# tester_rp2040.net
KiCad netlist of a schematic drawn in EAGLE
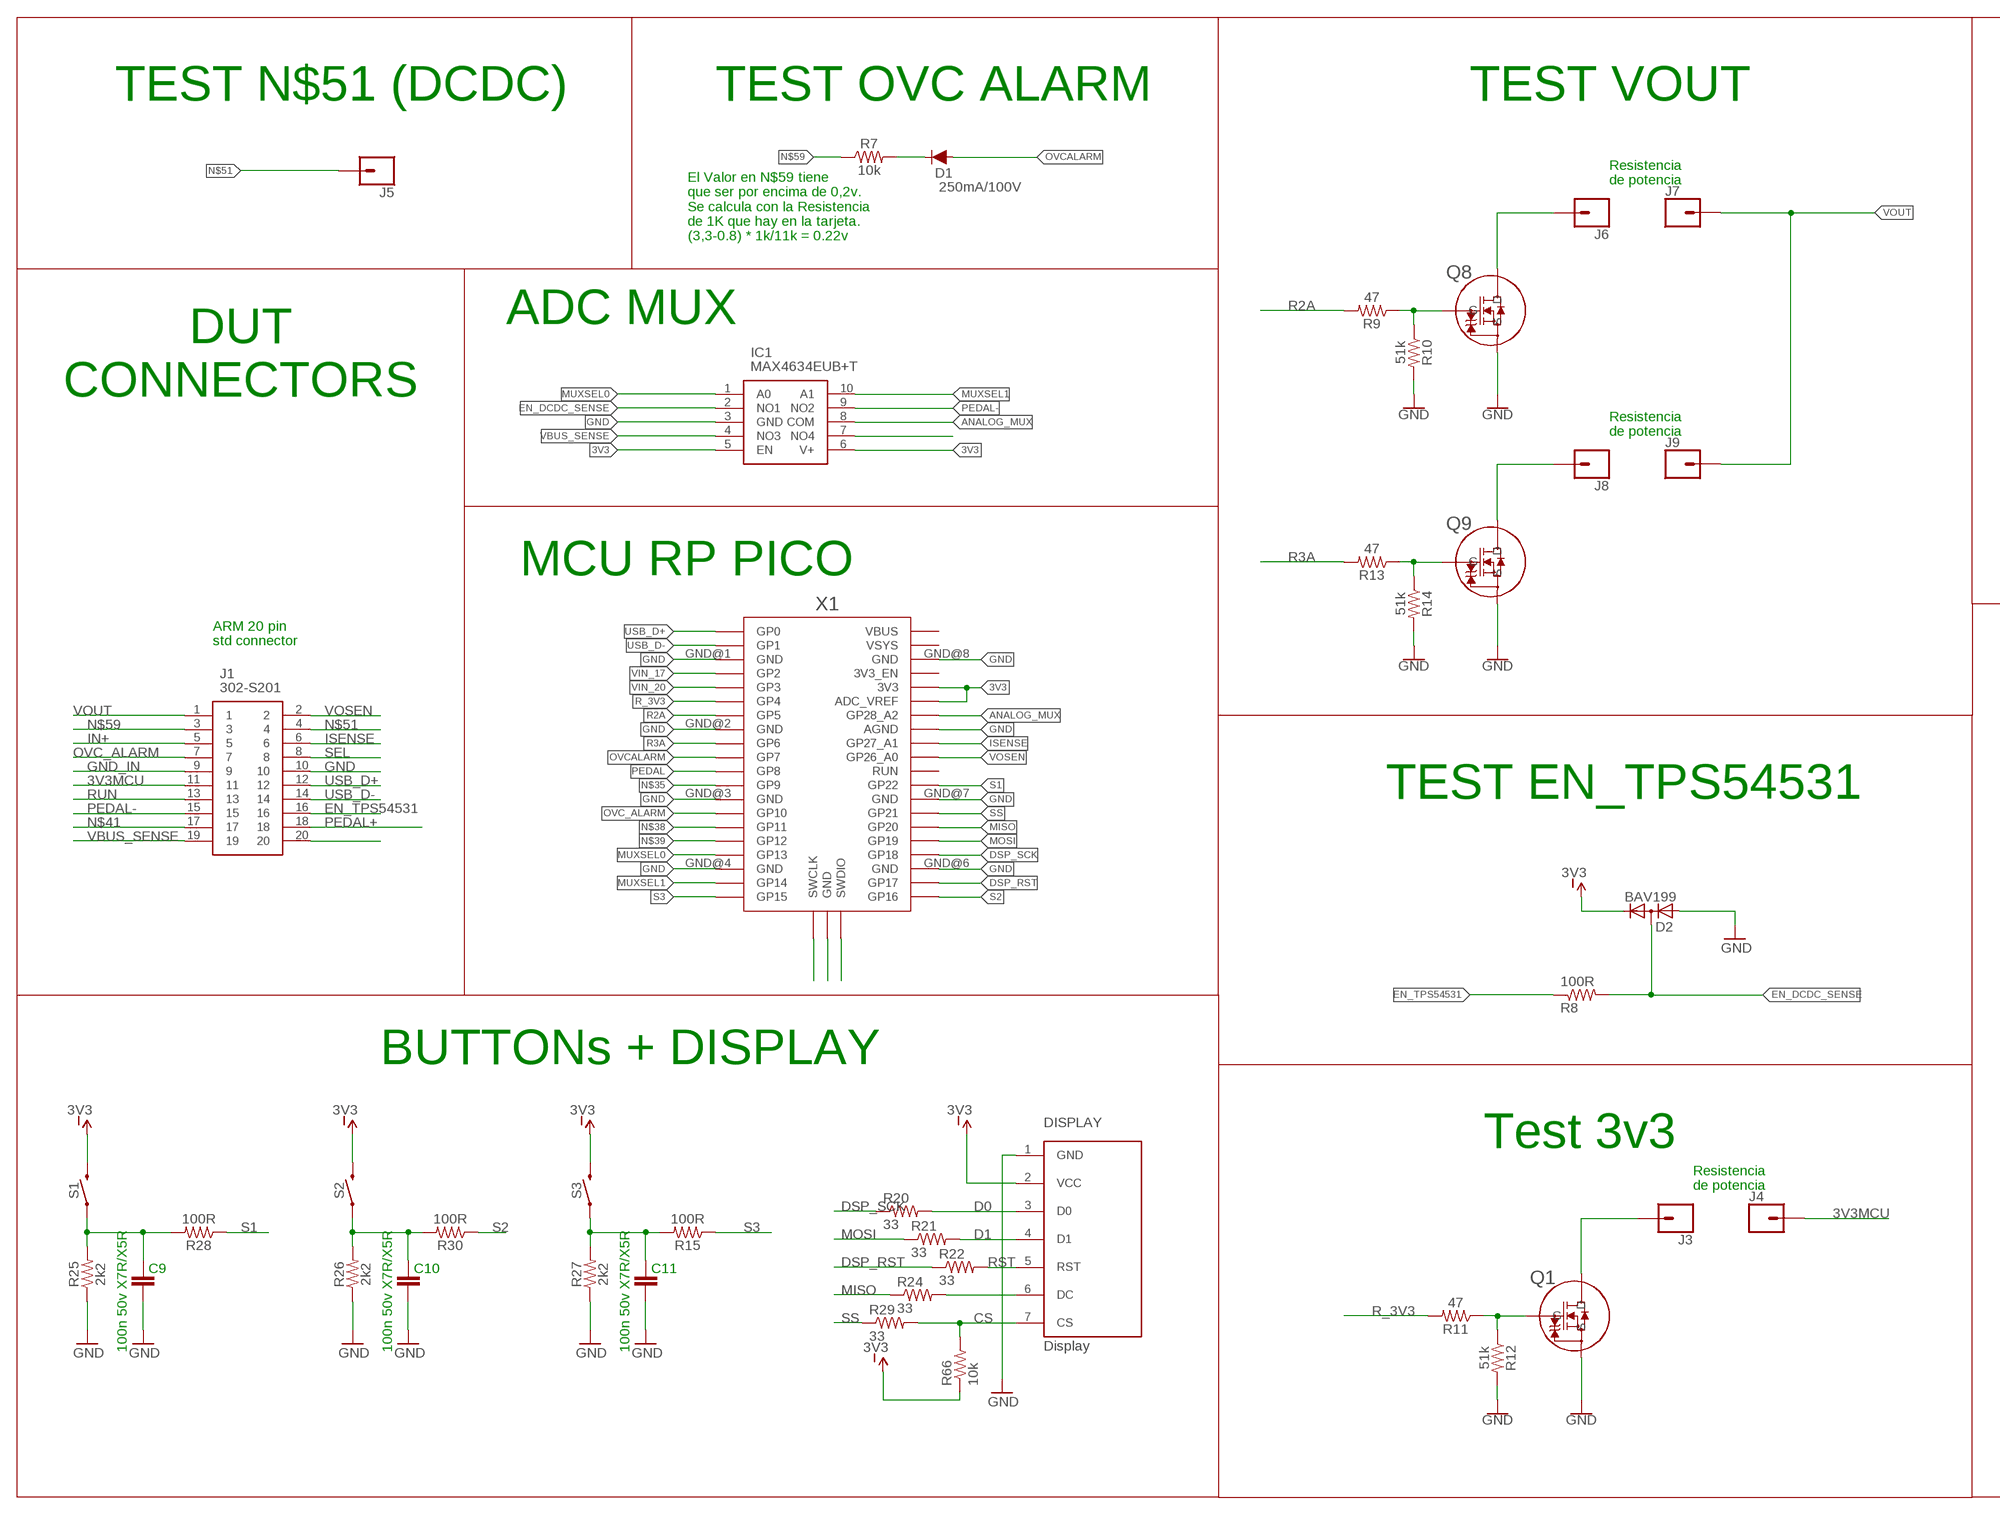
[diagram p0: schematic, sheet 1, part 1 of 2]
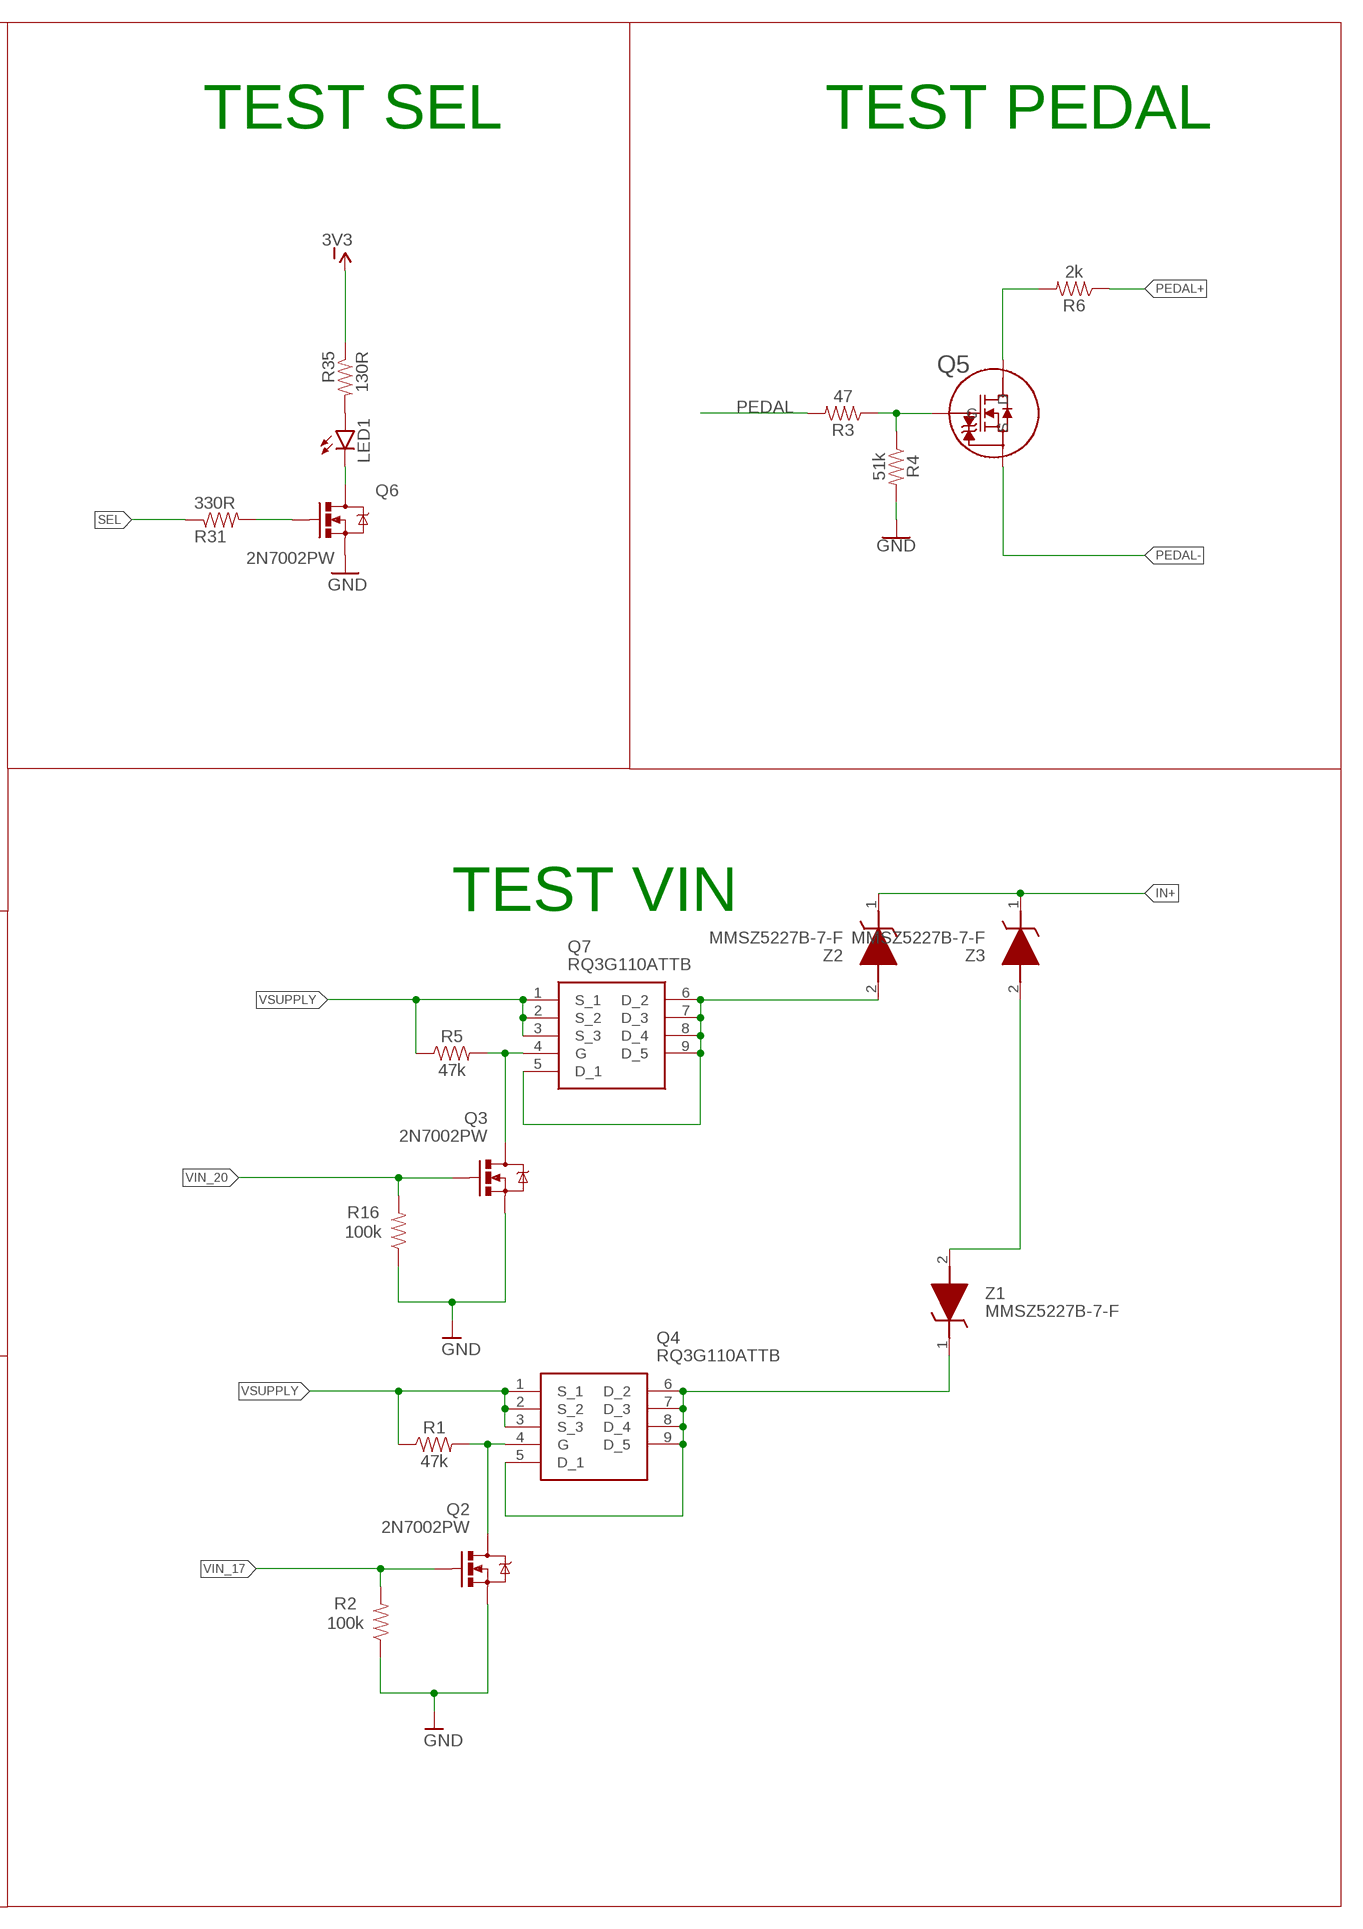
[diagram p1: schematic, sheet 1, part 2 of 2]

(export (version "E")
  (design (tool "Eeschema 10.0.6"))
  (components
    (comp (ref "C9")
      (value "100n 50v X7R/X5R")
      (footprint "eagle-import:0805")
      (libsource (lib "eagle-import") (part "CAP0805"))
    )
    (comp (ref "C10")
      (value "100n 50v X7R/X5R")
      (footprint "eagle-import:0805")
      (libsource (lib "eagle-import") (part "CAP0805"))
    )
    (comp (ref "C11")
      (value "100n 50v X7R/X5R")
      (footprint "eagle-import:0805")
      (libsource (lib "eagle-import") (part "CAP0805"))
    )
    (comp (ref "D1")
      (value "250mA/100V")
      (footprint "eagle-import:SOD-323")
      (libsource (lib "eagle-import") (part "DIODE-BAS16J"))
    )
    (comp (ref "D2")
      (value "BAV199")
      (footprint "eagle-import:SOT23")
      (libsource (lib "eagle-import") (part "BAV199"))
    )
    (comp (ref "DISPLAY")
      (value "Display")
      (footprint "eagle-import:OLED_LCD")
      (libsource (lib "eagle-import") (part "OLED_LCD"))
    )
    (comp (ref "IC1")
      (value "MAX4634EUB+T")
      (footprint "eagle-import:SOP50P490X110-10N")
      (fields (field (name "MOUSER_PART_NUMBER") "700-MAX4634EUBT"))
      (libsource (lib "eagle-import") (part "MAX4634EUB+T"))
    )
    (comp (ref "J1")
      (value "302-S201")
      (footprint "eagle-import:SHDR20W66P254_2X10_3300X905X90")
      (libsource (lib "eagle-import") (part "302-S201"))
    )
    (comp (ref "J3")
      (value "CONN_01")
      (footprint "eagle-import:1X01")
      (libsource (lib "eagle-import") (part "CONN_01"))
    )
    (comp (ref "J4")
      (value "CONN_01")
      (footprint "eagle-import:1X01")
      (libsource (lib "eagle-import") (part "CONN_01"))
    )
    (comp (ref "J5")
      (value "CONN_01")
      (footprint "eagle-import:1X01")
      (libsource (lib "eagle-import") (part "CONN_01"))
    )
    (comp (ref "J6")
      (value "CONN_01")
      (footprint "eagle-import:1X01")
      (libsource (lib "eagle-import") (part "CONN_01"))
    )
    (comp (ref "J7")
      (value "CONN_01")
      (footprint "eagle-import:1X01")
      (libsource (lib "eagle-import") (part "CONN_01"))
    )
    (comp (ref "J8")
      (value "CONN_01")
      (footprint "eagle-import:1X01")
      (libsource (lib "eagle-import") (part "CONN_01"))
    )
    (comp (ref "J9")
      (value "CONN_01")
      (footprint "eagle-import:1X01")
      (libsource (lib "eagle-import") (part "CONN_01"))
    )
    (comp (ref "LED1")
      (value "LED3MM")
      (footprint "eagle-import:LED3MM")
      (libsource (lib "eagle-import") (part "LED3MM"))
    )
    (comp (ref "Q1")
      (value "PJA3416AE_R1_00001")
      (footprint "eagle-import:SOT23_PJA3416_PNJ")
      (fields (field (name "COPYRIGHT") "Copyright (C) 2022 Ultra Librarian. All rights reserved."))
      (libsource (lib "eagle-import") (part "PJA3416AE_R1_00001"))
    )
    (comp (ref "Q2")
      (value "2N7002PW")
      (footprint "eagle-import:SOT323")
      (libsource (lib "eagle-import") (part "MOSFET-NCHANNEL2N7002PW"))
    )
    (comp (ref "Q3")
      (value "2N7002PW")
      (footprint "eagle-import:SOT323")
      (libsource (lib "eagle-import") (part "MOSFET-NCHANNEL2N7002PW"))
    )
    (comp (ref "Q4")
      (value "RQ3G110ATTB")
      (footprint "eagle-import:RQ3G110ATTB")
      (fields (field (name "MOUSER_PART_NUMBER") "755-RQ3G110ATTB"))
      (libsource (lib "eagle-import") (part "RQ3G110ATTB"))
    )
    (comp (ref "Q5")
      (value "PJA3416AE_R1_00001")
      (footprint "eagle-import:SOT23_PJA3416_PNJ")
      (fields (field (name "COPYRIGHT") "Copyright (C) 2022 Ultra Librarian. All rights reserved."))
      (libsource (lib "eagle-import") (part "PJA3416AE_R1_00001"))
    )
    (comp (ref "Q6")
      (value "2N7002PW")
      (footprint "eagle-import:SOT323")
      (libsource (lib "eagle-import") (part "MOSFET-NCHANNEL2N7002PW"))
    )
    (comp (ref "Q7")
      (value "RQ3G110ATTB")
      (footprint "eagle-import:RQ3G110ATTB")
      (fields (field (name "MOUSER_PART_NUMBER") "755-RQ3G110ATTB"))
      (libsource (lib "eagle-import") (part "RQ3G110ATTB"))
    )
    (comp (ref "Q8")
      (value "PJA3416AE_R1_00001")
      (footprint "eagle-import:SOT23_PJA3416_PNJ")
      (fields (field (name "COPYRIGHT") "Copyright (C) 2022 Ultra Librarian. All rights reserved."))
      (libsource (lib "eagle-import") (part "PJA3416AE_R1_00001"))
    )
    (comp (ref "Q9")
      (value "PJA3416AE_R1_00001")
      (footprint "eagle-import:SOT23_PJA3416_PNJ")
      (fields (field (name "COPYRIGHT") "Copyright (C) 2022 Ultra Librarian. All rights reserved."))
      (libsource (lib "eagle-import") (part "PJA3416AE_R1_00001"))
    )
    (comp (ref "R1")
      (value "47k")
      (footprint "eagle-import:0402")
      (libsource (lib "eagle-import") (part "RESISTOR0402"))
    )
    (comp (ref "R2")
      (value "100k")
      (footprint "eagle-import:0402")
      (libsource (lib "eagle-import") (part "RESISTOR0402"))
    )
    (comp (ref "R3")
      (value "47")
      (footprint "eagle-import:0805")
      (libsource (lib "eagle-import") (part "RESISTOR0805"))
    )
    (comp (ref "R4")
      (value "51k")
      (footprint "eagle-import:0805")
      (libsource (lib "eagle-import") (part "RESISTOR0805"))
    )
    (comp (ref "R5")
      (value "47k")
      (footprint "eagle-import:0402")
      (libsource (lib "eagle-import") (part "RESISTOR0402"))
    )
    (comp (ref "R6")
      (value "2k")
      (footprint "eagle-import:0805")
      (libsource (lib "eagle-import") (part "RESISTOR0805"))
    )
    (comp (ref "R7")
      (value "10k")
      (footprint "eagle-import:0805")
      (libsource (lib "eagle-import") (part "RESISTOR0805"))
    )
    (comp (ref "R8")
      (value "100R")
      (footprint "eagle-import:0805")
      (libsource (lib "eagle-import") (part "RESISTOR0805"))
    )
    (comp (ref "R9")
      (value "47")
      (footprint "eagle-import:0805")
      (libsource (lib "eagle-import") (part "RESISTOR0805"))
    )
    (comp (ref "R10")
      (value "51k")
      (footprint "eagle-import:0805")
      (libsource (lib "eagle-import") (part "RESISTOR0805"))
    )
    (comp (ref "R11")
      (value "47")
      (footprint "eagle-import:0805")
      (libsource (lib "eagle-import") (part "RESISTOR0805"))
    )
    (comp (ref "R12")
      (value "51k")
      (footprint "eagle-import:0805")
      (libsource (lib "eagle-import") (part "RESISTOR0805"))
    )
    (comp (ref "R13")
      (value "47")
      (footprint "eagle-import:0805")
      (libsource (lib "eagle-import") (part "RESISTOR0805"))
    )
    (comp (ref "R14")
      (value "51k")
      (footprint "eagle-import:0805")
      (libsource (lib "eagle-import") (part "RESISTOR0805"))
    )
    (comp (ref "R15")
      (value "100R")
      (footprint "eagle-import:0805")
      (libsource (lib "eagle-import") (part "RESISTOR0805"))
    )
    (comp (ref "R16")
      (value "100k")
      (footprint "eagle-import:0402")
      (libsource (lib "eagle-import") (part "RESISTOR0402"))
    )
    (comp (ref "R20")
      (value "33")
      (footprint "eagle-import:0805")
      (libsource (lib "eagle-import") (part "RESISTOR0805"))
    )
    (comp (ref "R21")
      (value "33")
      (footprint "eagle-import:0805")
      (libsource (lib "eagle-import") (part "RESISTOR0805"))
    )
    (comp (ref "R22")
      (value "33")
      (footprint "eagle-import:0805")
      (libsource (lib "eagle-import") (part "RESISTOR0805"))
    )
    (comp (ref "R24")
      (value "33")
      (footprint "eagle-import:0805")
      (libsource (lib "eagle-import") (part "RESISTOR0805"))
    )
    (comp (ref "R25")
      (value "2k2")
      (footprint "eagle-import:0805")
      (libsource (lib "eagle-import") (part "RESISTOR0805"))
    )
    (comp (ref "R26")
      (value "2k2")
      (footprint "eagle-import:0805")
      (libsource (lib "eagle-import") (part "RESISTOR0805"))
    )
    (comp (ref "R27")
      (value "2k2")
      (footprint "eagle-import:0805")
      (libsource (lib "eagle-import") (part "RESISTOR0805"))
    )
    (comp (ref "R28")
      (value "100R")
      (footprint "eagle-import:0805")
      (libsource (lib "eagle-import") (part "RESISTOR0805"))
    )
    (comp (ref "R29")
      (value "33")
      (footprint "eagle-import:0805")
      (libsource (lib "eagle-import") (part "RESISTOR0805"))
    )
    (comp (ref "R30")
      (value "100R")
      (footprint "eagle-import:0805")
      (libsource (lib "eagle-import") (part "RESISTOR0805"))
    )
    (comp (ref "R31")
      (value "330R")
      (footprint "eagle-import:0805")
      (libsource (lib "eagle-import") (part "RESISTOR0805"))
    )
    (comp (ref "R35")
      (value "130R")
      (footprint "eagle-import:0805")
      (libsource (lib "eagle-import") (part "RESISTOR0805"))
    )
    (comp (ref "R66")
      (value "10k")
      (footprint "eagle-import:0805")
      (libsource (lib "eagle-import") (part "RESISTOR0805"))
    )
    (comp (ref "S1")
      (value "MOMENTARY-SWITCH-SPST-SMD-5.2MM")
      (footprint "eagle-import:TACTILE_SWITCH_SMD_5.2MM")
      (libsource (lib "eagle-import") (part "MOMENTARY-SWITCH-SPST-SMD-5.2MM"))
    )
    (comp (ref "S2")
      (value "MOMENTARY-SWITCH-SPST-SMD-5.2MM")
      (footprint "eagle-import:TACTILE_SWITCH_SMD_5.2MM")
      (libsource (lib "eagle-import") (part "MOMENTARY-SWITCH-SPST-SMD-5.2MM"))
    )
    (comp (ref "S3")
      (value "MOMENTARY-SWITCH-SPST-SMD-5.2MM")
      (footprint "eagle-import:TACTILE_SWITCH_SMD_5.2MM")
      (libsource (lib "eagle-import") (part "MOMENTARY-SWITCH-SPST-SMD-5.2MM"))
    )
    (comp (ref "X1")
      (value "RPI_PICO_IG-TH")
      (footprint "eagle-import:RPI_PICO_TH")
      (libsource (lib "eagle-import") (part "RPI_PICO_IG-TH"))
    )
    (comp (ref "Z1")
      (value "MMSZ5227B-7-F")
      (footprint "eagle-import:SOD3716X135N")
      (fields (field (name "MOUSER_PART_NUMBER") "621-MMSZ5227B-F"))
      (libsource (lib "eagle-import") (part "MMSZ5227B-7-F"))
    )
    (comp (ref "Z2")
      (value "MMSZ5227B-7-F")
      (footprint "eagle-import:SOD3716X135N")
      (fields (field (name "MOUSER_PART_NUMBER") "621-MMSZ5227B-F"))
      (libsource (lib "eagle-import") (part "MMSZ5227B-7-F"))
    )
    (comp (ref "Z3")
      (value "MMSZ5227B-7-F")
      (footprint "eagle-import:SOD3716X135N")
      (fields (field (name "MOUSER_PART_NUMBER") "621-MMSZ5227B-F"))
      (libsource (lib "eagle-import") (part "MMSZ5227B-7-F"))
    )
  )
  (nets
    (net (code "1") (name "/3V3MCU") (class "Default")
      (node (ref "J1") (pin "11") (pinfunction "11_11") (pintype "bidirectional"))
      (node (ref "J4") (pin "1") (pinfunction "1_1") (pintype "passive"))
    )
    (net (code "2") (name "/CS") (class "Default")
      (node (ref "DISPLAY") (pin "7") (pinfunction "CS_7") (pintype "bidirectional"))
      (node (ref "R29") (pin "2") (pinfunction "2_2") (pintype "passive"))
      (node (ref "R66") (pin "2") (pinfunction "2_2") (pintype "passive"))
    )
    (net (code "3") (name "/D0") (class "Default")
      (node (ref "DISPLAY") (pin "3") (pinfunction "D0_3") (pintype "bidirectional"))
      (node (ref "R20") (pin "2") (pinfunction "2_2") (pintype "passive"))
    )
    (net (code "4") (name "/D1") (class "Default")
      (node (ref "DISPLAY") (pin "4") (pinfunction "D1_4") (pintype "bidirectional"))
      (node (ref "R21") (pin "2") (pinfunction "2_2") (pintype "passive"))
    )
    (net (code "5") (name "/GND_IN") (class "Default")
      (node (ref "J1") (pin "9") (pinfunction "9_9") (pintype "bidirectional"))
    )
    (net (code "6") (name "/N$41") (class "Default")
      (node (ref "J1") (pin "17") (pinfunction "17_17") (pintype "bidirectional"))
    )
    (net (code "7") (name "/RST") (class "Default")
      (node (ref "DISPLAY") (pin "5") (pinfunction "RST_5") (pintype "bidirectional"))
      (node (ref "R22") (pin "2") (pinfunction "2_2") (pintype "passive"))
    )
    (net (code "8") (name "/RUN") (class "Default")
      (node (ref "J1") (pin "13") (pinfunction "13_13") (pintype "bidirectional"))
    )
    (net (code "9") (name "3V3") (class "Default")
      (node (ref "D2") (pin "2") (pinfunction "C_2") (pintype "passive"))
      (node (ref "DISPLAY") (pin "2") (pinfunction "VCC_2") (pintype "bidirectional"))
      (node (ref "IC1") (pin "5") (pinfunction "EN_5") (pintype "bidirectional"))
      (node (ref "IC1") (pin "6") (pinfunction "V+_6") (pintype "bidirectional"))
      (node (ref "R35") (pin "1") (pinfunction "1_1") (pintype "passive"))
      (node (ref "R66") (pin "1") (pinfunction "1_1") (pintype "passive"))
      (node (ref "S1") (pin "3") (pinfunction "2_3") (pintype "passive"))
      (node (ref "S2") (pin "3") (pinfunction "2_3") (pintype "passive"))
      (node (ref "S3") (pin "3") (pinfunction "2_3") (pintype "passive"))
      (node (ref "X1") (pin "3V3") (pinfunction "3V3_3V3") (pintype "bidirectional"))
      (node (ref "X1") (pin "ADC_VREF") (pinfunction "ADC_VREF_ADC_VREF") (pintype "bidirectional"))
    )
    (net (code "10") (name "ANALOG_MUX") (class "Default")
      (node (ref "IC1") (pin "8") (pinfunction "COM_8") (pintype "bidirectional"))
      (node (ref "X1") (pin "GP28_A2") (pinfunction "GP28_A2_GP28_A2") (pintype "bidirectional"))
    )
    (net (code "11") (name "DSP_RST") (class "Default")
      (node (ref "R22") (pin "1") (pinfunction "1_1") (pintype "passive"))
      (node (ref "X1") (pin "GP17") (pinfunction "GP17_GP17") (pintype "bidirectional"))
    )
    (net (code "12") (name "DSP_SCK") (class "Default")
      (node (ref "R20") (pin "1") (pinfunction "1_1") (pintype "passive"))
      (node (ref "X1") (pin "GP18") (pinfunction "GP18_GP18") (pintype "bidirectional"))
    )
    (net (code "13") (name "EN_DCDC_SENSE") (class "Default")
      (node (ref "D2") (pin "3") (pinfunction "AC_3") (pintype "passive"))
      (node (ref "IC1") (pin "2") (pinfunction "NO1_2") (pintype "bidirectional"))
      (node (ref "R8") (pin "2") (pinfunction "2_2") (pintype "passive"))
    )
    (net (code "14") (name "EN_TPS54531") (class "Default")
      (node (ref "J1") (pin "16") (pinfunction "16_16") (pintype "bidirectional"))
      (node (ref "R8") (pin "1") (pinfunction "1_1") (pintype "passive"))
    )
    (net (code "15") (name "GND") (class "Default")
      (node (ref "C10") (pin "1") (pinfunction "1_1") (pintype "passive"))
      (node (ref "C11") (pin "1") (pinfunction "1_1") (pintype "passive"))
      (node (ref "C9") (pin "1") (pinfunction "1_1") (pintype "passive"))
      (node (ref "D2") (pin "1") (pinfunction "A_1") (pintype "passive"))
      (node (ref "DISPLAY") (pin "1") (pinfunction "GND_1") (pintype "bidirectional"))
      (node (ref "IC1") (pin "3") (pinfunction "GND_3") (pintype "bidirectional"))
      (node (ref "J1") (pin "10") (pinfunction "10_10") (pintype "bidirectional"))
      (node (ref "Q1") (pin "2") (pinfunction "S_2") (pintype "passive"))
      (node (ref "Q2") (pin "2") (pinfunction "S_2") (pintype "passive"))
      (node (ref "Q3") (pin "2") (pinfunction "S_2") (pintype "passive"))
      (node (ref "Q6") (pin "2") (pinfunction "S_2") (pintype "passive"))
      (node (ref "Q8") (pin "2") (pinfunction "S_2") (pintype "passive"))
      (node (ref "Q9") (pin "2") (pinfunction "S_2") (pintype "passive"))
      (node (ref "R10") (pin "2") (pinfunction "2_2") (pintype "passive"))
      (node (ref "R12") (pin "2") (pinfunction "2_2") (pintype "passive"))
      (node (ref "R14") (pin "2") (pinfunction "2_2") (pintype "passive"))
      (node (ref "R16") (pin "1") (pinfunction "1_1") (pintype "passive"))
      (node (ref "R2") (pin "1") (pinfunction "1_1") (pintype "passive"))
      (node (ref "R25") (pin "1") (pinfunction "1_1") (pintype "passive"))
      (node (ref "R26") (pin "1") (pinfunction "1_1") (pintype "passive"))
      (node (ref "R27") (pin "1") (pinfunction "1_1") (pintype "passive"))
      (node (ref "R4") (pin "2") (pinfunction "2_2") (pintype "passive"))
      (node (ref "X1") (pin "AGND") (pinfunction "AGND_AGND") (pintype "bidirectional"))
      (node (ref "X1") (pin "GND@1") (pinfunction "GND_GND@1") (pintype "bidirectional"))
      (node (ref "X1") (pin "GND@2") (pinfunction "GND_GND@2") (pintype "bidirectional"))
      (node (ref "X1") (pin "GND@3") (pinfunction "GND_GND@3") (pintype "bidirectional"))
      (node (ref "X1") (pin "GND@4") (pinfunction "GND_GND@4") (pintype "bidirectional"))
      (node (ref "X1") (pin "GND@6") (pinfunction "GND_GND@6") (pintype "bidirectional"))
      (node (ref "X1") (pin "GND@7") (pinfunction "GND_GND@7") (pintype "bidirectional"))
      (node (ref "X1") (pin "GND@8") (pinfunction "GND_GND@8") (pintype "bidirectional"))
    )
    (net (code "16") (name "IN+") (class "Default")
      (node (ref "J1") (pin "5") (pinfunction "5_5") (pintype "bidirectional"))
      (node (ref "Q7") (pin "5") (pinfunction "D_1_5") (pintype "bidirectional"))
      (node (ref "Q7") (pin "6") (pinfunction "D_2_6") (pintype "bidirectional"))
      (node (ref "Q7") (pin "7") (pinfunction "D_3_7") (pintype "bidirectional"))
      (node (ref "Q7") (pin "8") (pinfunction "D_4_8") (pintype "bidirectional"))
      (node (ref "Q7") (pin "9") (pinfunction "D_5_9") (pintype "bidirectional"))
      (node (ref "Z2") (pin "1") (pinfunction "K_1") (pintype "bidirectional"))
      (node (ref "Z2") (pin "2") (pinfunction "A_2") (pintype "bidirectional"))
      (node (ref "Z3") (pin "1") (pinfunction "K_1") (pintype "bidirectional"))
    )
    (net (code "17") (name "ISENSE") (class "Default")
      (node (ref "J1") (pin "6") (pinfunction "6_6") (pintype "bidirectional"))
      (node (ref "X1") (pin "GP27_A1") (pinfunction "GP27_A1_GP27_A1") (pintype "bidirectional"))
    )
    (net (code "18") (name "MISO") (class "Default")
      (node (ref "R24") (pin "1") (pinfunction "1_1") (pintype "passive"))
      (node (ref "X1") (pin "GP20") (pinfunction "GP20_GP20") (pintype "bidirectional"))
    )
    (net (code "19") (name "MOSI") (class "Default")
      (node (ref "R21") (pin "1") (pinfunction "1_1") (pintype "passive"))
      (node (ref "X1") (pin "GP19") (pinfunction "GP19_GP19") (pintype "bidirectional"))
    )
    (net (code "20") (name "MUXSEL0") (class "Default")
      (node (ref "IC1") (pin "1") (pinfunction "A0_1") (pintype "bidirectional"))
      (node (ref "X1") (pin "GP13") (pinfunction "GP13_GP13") (pintype "bidirectional"))
    )
    (net (code "21") (name "MUXSEL1") (class "Default")
      (node (ref "IC1") (pin "10") (pinfunction "A1_10") (pintype "bidirectional"))
      (node (ref "X1") (pin "GP14") (pinfunction "GP14_GP14") (pintype "bidirectional"))
    )
    (net (code "22") (name "N$35") (class "Default")
      (node (ref "X1") (pin "GP9") (pinfunction "GP9_GP9") (pintype "bidirectional"))
    )
    (net (code "23") (name "N$38") (class "Default")
      (node (ref "X1") (pin "GP11") (pinfunction "GP11_GP11") (pintype "bidirectional"))
    )
    (net (code "24") (name "N$39") (class "Default")
      (node (ref "X1") (pin "GP12") (pinfunction "GP12_GP12") (pintype "bidirectional"))
    )
    (net (code "25") (name "N$51") (class "Default")
      (node (ref "J1") (pin "4") (pinfunction "4_4") (pintype "bidirectional"))
      (node (ref "J5") (pin "1") (pinfunction "1_1") (pintype "passive"))
    )
    (net (code "26") (name "N$59") (class "Default")
      (node (ref "J1") (pin "3") (pinfunction "3_3") (pintype "bidirectional"))
      (node (ref "R7") (pin "1") (pinfunction "1_1") (pintype "passive"))
    )
    (net (code "27") (name "Net-(C9-Pad2)") (class "Default")
      (node (ref "C9") (pin "2") (pinfunction "2_2") (pintype "passive"))
      (node (ref "R25") (pin "2") (pinfunction "2_2") (pintype "passive"))
      (node (ref "R28") (pin "2") (pinfunction "2_2") (pintype "passive"))
      (node (ref "S1") (pin "1") (pinfunction "1_1") (pintype "passive"))
    )
    (net (code "28") (name "Net-(C10-Pad2)") (class "Default")
      (node (ref "C10") (pin "2") (pinfunction "2_2") (pintype "passive"))
      (node (ref "R26") (pin "2") (pinfunction "2_2") (pintype "passive"))
      (node (ref "R30") (pin "2") (pinfunction "2_2") (pintype "passive"))
      (node (ref "S2") (pin "1") (pinfunction "1_1") (pintype "passive"))
    )
    (net (code "29") (name "Net-(C11-Pad2)") (class "Default")
      (node (ref "C11") (pin "2") (pinfunction "2_2") (pintype "passive"))
      (node (ref "R15") (pin "2") (pinfunction "2_2") (pintype "passive"))
      (node (ref "R27") (pin "2") (pinfunction "2_2") (pintype "passive"))
      (node (ref "S3") (pin "1") (pinfunction "1_1") (pintype "passive"))
    )
    (net (code "30") (name "Net-(D1-PadC)") (class "Default")
      (node (ref "D1") (pin "C") (pinfunction "C_C") (pintype "passive"))
      (node (ref "R7") (pin "2") (pinfunction "2_2") (pintype "passive"))
    )
    (net (code "31") (name "Net-(DISPLAY-DC)") (class "Default")
      (node (ref "DISPLAY") (pin "6") (pinfunction "DC_6") (pintype "bidirectional"))
      (node (ref "R24") (pin "2") (pinfunction "2_2") (pintype "passive"))
    )
    (net (code "32") (name "Net-(LED1-C)") (class "Default")
      (node (ref "LED1") (pin "K") (pinfunction "C_K") (pintype "passive"))
      (node (ref "Q6") (pin "3") (pinfunction "D_3") (pintype "passive"))
    )
    (net (code "33") (name "Net-(LED1-PadA)") (class "Default")
      (node (ref "LED1") (pin "A") (pinfunction "A_A") (pintype "passive"))
      (node (ref "R35") (pin "2") (pinfunction "2_2") (pintype "passive"))
    )
    (net (code "34") (name "Net-(Q1-D)") (class "Default")
      (node (ref "J3") (pin "1") (pinfunction "1_1") (pintype "passive"))
      (node (ref "Q1") (pin "3") (pinfunction "D_3") (pintype "passive"))
    )
    (net (code "35") (name "Net-(Q1-G)") (class "Default")
      (node (ref "Q1") (pin "1") (pinfunction "G_1") (pintype "passive"))
      (node (ref "R11") (pin "1") (pinfunction "1_1") (pintype "passive"))
      (node (ref "R12") (pin "1") (pinfunction "1_1") (pintype "passive"))
    )
    (net (code "36") (name "Net-(Q2-D)") (class "Default")
      (node (ref "Q2") (pin "3") (pinfunction "D_3") (pintype "passive"))
      (node (ref "Q4") (pin "4") (pinfunction "G_4") (pintype "bidirectional"))
      (node (ref "R1") (pin "2") (pinfunction "2_2") (pintype "passive"))
    )
    (net (code "37") (name "Net-(Q3-D)") (class "Default")
      (node (ref "Q3") (pin "3") (pinfunction "D_3") (pintype "passive"))
      (node (ref "Q7") (pin "4") (pinfunction "G_4") (pintype "bidirectional"))
      (node (ref "R5") (pin "2") (pinfunction "2_2") (pintype "passive"))
    )
    (net (code "38") (name "Net-(Q4-D_1)") (class "Default")
      (node (ref "Q4") (pin "5") (pinfunction "D_1_5") (pintype "bidirectional"))
      (node (ref "Q4") (pin "6") (pinfunction "D_2_6") (pintype "bidirectional"))
      (node (ref "Q4") (pin "7") (pinfunction "D_3_7") (pintype "bidirectional"))
      (node (ref "Q4") (pin "8") (pinfunction "D_4_8") (pintype "bidirectional"))
      (node (ref "Q4") (pin "9") (pinfunction "D_5_9") (pintype "bidirectional"))
      (node (ref "Z1") (pin "1") (pinfunction "K_1") (pintype "bidirectional"))
    )
    (net (code "39") (name "Net-(Q5-D)") (class "Default")
      (node (ref "Q5") (pin "3") (pinfunction "D_3") (pintype "passive"))
      (node (ref "R6") (pin "2") (pinfunction "2_2") (pintype "passive"))
    )
    (net (code "40") (name "Net-(Q5-G)") (class "Default")
      (node (ref "Q5") (pin "1") (pinfunction "G_1") (pintype "passive"))
      (node (ref "R3") (pin "1") (pinfunction "1_1") (pintype "passive"))
      (node (ref "R4") (pin "1") (pinfunction "1_1") (pintype "passive"))
    )
    (net (code "41") (name "Net-(Q6-G)") (class "Default")
      (node (ref "Q6") (pin "1") (pinfunction "G_1") (pintype "passive"))
      (node (ref "R31") (pin "2") (pinfunction "2_2") (pintype "passive"))
    )
    (net (code "42") (name "Net-(Q8-D)") (class "Default")
      (node (ref "J6") (pin "1") (pinfunction "1_1") (pintype "passive"))
      (node (ref "Q8") (pin "3") (pinfunction "D_3") (pintype "passive"))
    )
    (net (code "43") (name "Net-(Q8-G)") (class "Default")
      (node (ref "Q8") (pin "1") (pinfunction "G_1") (pintype "passive"))
      (node (ref "R10") (pin "1") (pinfunction "1_1") (pintype "passive"))
      (node (ref "R9") (pin "1") (pinfunction "1_1") (pintype "passive"))
    )
    (net (code "44") (name "Net-(Q9-D)") (class "Default")
      (node (ref "J8") (pin "1") (pinfunction "1_1") (pintype "passive"))
      (node (ref "Q9") (pin "3") (pinfunction "D_3") (pintype "passive"))
    )
    (net (code "45") (name "Net-(Q9-G)") (class "Default")
      (node (ref "Q9") (pin "1") (pinfunction "G_1") (pintype "passive"))
      (node (ref "R13") (pin "1") (pinfunction "1_1") (pintype "passive"))
      (node (ref "R14") (pin "1") (pinfunction "1_1") (pintype "passive"))
    )
    (net (code "46") (name "Net-(Z1-A)") (class "Default")
      (node (ref "Z1") (pin "2") (pinfunction "A_2") (pintype "bidirectional"))
      (node (ref "Z3") (pin "2") (pinfunction "A_2") (pintype "bidirectional"))
    )
    (net (code "47") (name "OVCALARM") (class "Default")
      (node (ref "D1") (pin "A") (pinfunction "A_A") (pintype "passive"))
      (node (ref "X1") (pin "GP7") (pinfunction "GP7_GP7") (pintype "bidirectional"))
    )
    (net (code "48") (name "OVC_ALARM") (class "Default")
      (node (ref "J1") (pin "7") (pinfunction "7_7") (pintype "bidirectional"))
      (node (ref "X1") (pin "GP10") (pinfunction "GP10_GP10") (pintype "bidirectional"))
    )
    (net (code "49") (name "PEDAL") (class "Default")
      (node (ref "R3") (pin "2") (pinfunction "2_2") (pintype "passive"))
      (node (ref "X1") (pin "GP8") (pinfunction "GP8_GP8") (pintype "bidirectional"))
    )
    (net (code "50") (name "PEDAL+") (class "Default")
      (node (ref "J1") (pin "18") (pinfunction "18_18") (pintype "bidirectional"))
      (node (ref "R6") (pin "1") (pinfunction "1_1") (pintype "passive"))
    )
    (net (code "51") (name "PEDAL-") (class "Default")
      (node (ref "IC1") (pin "9") (pinfunction "NO2_9") (pintype "bidirectional"))
      (node (ref "J1") (pin "15") (pinfunction "15_15") (pintype "bidirectional"))
      (node (ref "Q5") (pin "2") (pinfunction "S_2") (pintype "passive"))
    )
    (net (code "52") (name "R2A") (class "Default")
      (node (ref "R9") (pin "2") (pinfunction "2_2") (pintype "passive"))
      (node (ref "X1") (pin "GP5") (pinfunction "GP5_GP5") (pintype "bidirectional"))
    )
    (net (code "53") (name "R3A") (class "Default")
      (node (ref "R13") (pin "2") (pinfunction "2_2") (pintype "passive"))
      (node (ref "X1") (pin "GP6") (pinfunction "GP6_GP6") (pintype "bidirectional"))
    )
    (net (code "54") (name "R_3V3") (class "Default")
      (node (ref "R11") (pin "2") (pinfunction "2_2") (pintype "passive"))
      (node (ref "X1") (pin "GP4") (pinfunction "GP4_GP4") (pintype "bidirectional"))
    )
    (net (code "55") (name "S1") (class "Default")
      (node (ref "R28") (pin "1") (pinfunction "1_1") (pintype "passive"))
      (node (ref "X1") (pin "GP22") (pinfunction "GP22_GP22") (pintype "bidirectional"))
    )
    (net (code "56") (name "S2") (class "Default")
      (node (ref "R30") (pin "1") (pinfunction "1_1") (pintype "passive"))
      (node (ref "X1") (pin "GP16") (pinfunction "GP16_GP16") (pintype "bidirectional"))
    )
    (net (code "57") (name "S3") (class "Default")
      (node (ref "R15") (pin "1") (pinfunction "1_1") (pintype "passive"))
      (node (ref "X1") (pin "GP15") (pinfunction "GP15_GP15") (pintype "bidirectional"))
    )
    (net (code "58") (name "SEL") (class "Default")
      (node (ref "J1") (pin "8") (pinfunction "8_8") (pintype "bidirectional"))
      (node (ref "R31") (pin "1") (pinfunction "1_1") (pintype "passive"))
    )
    (net (code "59") (name "SS") (class "Default")
      (node (ref "R29") (pin "1") (pinfunction "1_1") (pintype "passive"))
      (node (ref "X1") (pin "GP21") (pinfunction "GP21_GP21") (pintype "bidirectional"))
    )
    (net (code "60") (name "USB_D+") (class "Default")
      (node (ref "J1") (pin "12") (pinfunction "12_12") (pintype "bidirectional"))
      (node (ref "X1") (pin "GP0") (pinfunction "GP0_GP0") (pintype "bidirectional"))
    )
    (net (code "61") (name "USB_D-") (class "Default")
      (node (ref "J1") (pin "14") (pinfunction "14_14") (pintype "bidirectional"))
      (node (ref "X1") (pin "GP1") (pinfunction "GP1_GP1") (pintype "bidirectional"))
    )
    (net (code "62") (name "VBUS_SENSE") (class "Default")
      (node (ref "IC1") (pin "4") (pinfunction "NO3_4") (pintype "bidirectional"))
      (node (ref "J1") (pin "19") (pinfunction "19_19") (pintype "bidirectional"))
    )
    (net (code "63") (name "VIN_17") (class "Default")
      (node (ref "Q2") (pin "1") (pinfunction "G_1") (pintype "passive"))
      (node (ref "R2") (pin "2") (pinfunction "2_2") (pintype "passive"))
      (node (ref "X1") (pin "GP2") (pinfunction "GP2_GP2") (pintype "bidirectional"))
    )
    (net (code "64") (name "VIN_20") (class "Default")
      (node (ref "Q3") (pin "1") (pinfunction "G_1") (pintype "passive"))
      (node (ref "R16") (pin "2") (pinfunction "2_2") (pintype "passive"))
      (node (ref "X1") (pin "GP3") (pinfunction "GP3_GP3") (pintype "bidirectional"))
    )
    (net (code "65") (name "VOSEN") (class "Default")
      (node (ref "J1") (pin "2") (pinfunction "2_2") (pintype "bidirectional"))
      (node (ref "X1") (pin "GP26_A0") (pinfunction "GP26_A0_GP26_A0") (pintype "bidirectional"))
    )
    (net (code "66") (name "VOUT") (class "Default")
      (node (ref "J1") (pin "1") (pinfunction "1_1") (pintype "bidirectional"))
      (node (ref "J7") (pin "1") (pinfunction "1_1") (pintype "passive"))
      (node (ref "J9") (pin "1") (pinfunction "1_1") (pintype "passive"))
    )
    (net (code "67") (name "VSUPPLY") (class "Default")
      (node (ref "Q4") (pin "1") (pinfunction "S_1_1") (pintype "bidirectional"))
      (node (ref "Q4") (pin "2") (pinfunction "S_2_2") (pintype "bidirectional"))
      (node (ref "Q4") (pin "3") (pinfunction "S_3_3") (pintype "bidirectional"))
      (node (ref "Q7") (pin "1") (pinfunction "S_1_1") (pintype "bidirectional"))
      (node (ref "Q7") (pin "2") (pinfunction "S_2_2") (pintype "bidirectional"))
      (node (ref "Q7") (pin "3") (pinfunction "S_3_3") (pintype "bidirectional"))
      (node (ref "R1") (pin "1") (pinfunction "1_1") (pintype "passive"))
      (node (ref "R5") (pin "1") (pinfunction "1_1") (pintype "passive"))
    )
    (net (code "68") (name "unconnected-(IC1-NO4-Pad7)") (class "Default")
      (node (ref "IC1") (pin "7") (pinfunction "NO4_7") (pintype "bidirectional"))
    )
    (net (code "69") (name "unconnected-(J1-Pad20)") (class "Default")
      (node (ref "J1") (pin "20") (pinfunction "20_20") (pintype "bidirectional"))
    )
    (net (code "70") (name "unconnected-(X1-GND-PadGND@5)") (class "Default")
      (node (ref "X1") (pin "GND@5") (pinfunction "GND_GND@5") (pintype "bidirectional"))
    )
    (net (code "71") (name "unconnected-(X1-Pad3V3_EN)") (class "Default")
      (node (ref "X1") (pin "3V3_EN") (pinfunction "3V3_EN_3V3_EN") (pintype "bidirectional"))
    )
    (net (code "72") (name "unconnected-(X1-PadRUN)") (class "Default")
      (node (ref "X1") (pin "RUN") (pinfunction "RUN_RUN") (pintype "bidirectional"))
    )
    (net (code "73") (name "unconnected-(X1-PadSWCLK)") (class "Default")
      (node (ref "X1") (pin "SWCLK") (pinfunction "SWCLK_SWCLK") (pintype "bidirectional"))
    )
    (net (code "74") (name "unconnected-(X1-PadSWDIO)") (class "Default")
      (node (ref "X1") (pin "SWDIO") (pinfunction "SWDIO_SWDIO") (pintype "bidirectional"))
    )
    (net (code "75") (name "unconnected-(X1-PadVBUS)") (class "Default")
      (node (ref "X1") (pin "VBUS") (pinfunction "VBUS_VBUS") (pintype "bidirectional"))
    )
    (net (code "76") (name "unconnected-(X1-PadVSYS)") (class "Default")
      (node (ref "X1") (pin "VSYS") (pinfunction "VSYS_VSYS") (pintype "bidirectional"))
    )
  )
)
